# MAVCam.net
KiCad netlist of a schematic drawn in EAGLE
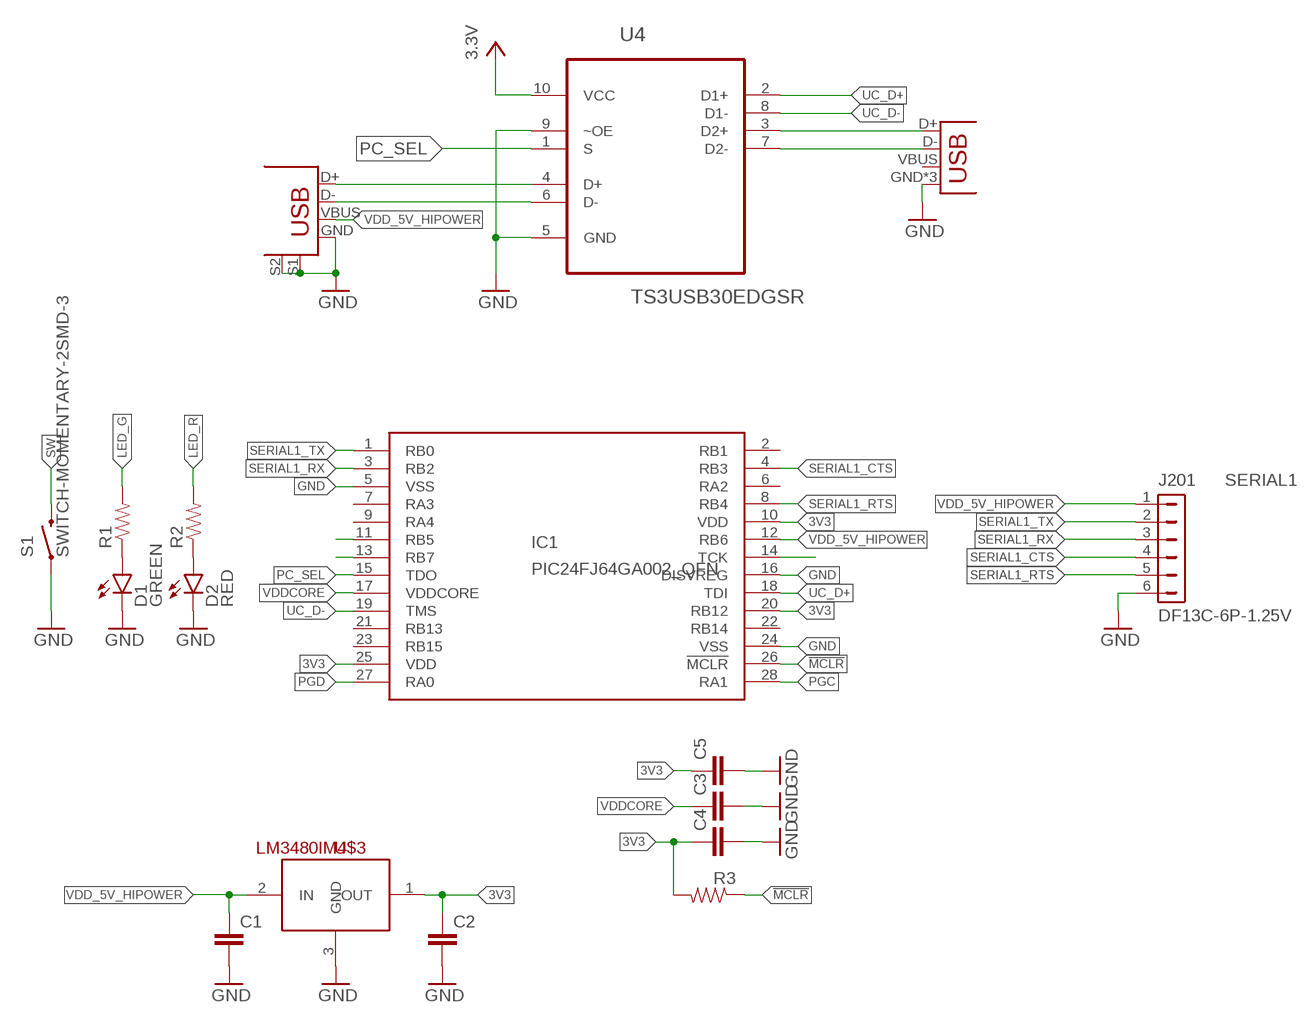
[diagram p0: schematic, sheet 1]

(export (version "E")
  (design (tool "Eeschema 10.0.6"))
  (components
    (comp (ref "C1")
      (value "CAP0603-CAP")
      (footprint "eagle-import:0603-CAP")
      (libsource (lib "eagle-import") (part "CAP0603-CAP"))
    )
    (comp (ref "C2")
      (value "CAP0603-CAP")
      (footprint "eagle-import:0603-CAP")
      (libsource (lib "eagle-import") (part "CAP0603-CAP"))
    )
    (comp (ref "C3")
      (value "CAP0603-CAP")
      (footprint "eagle-import:0603-CAP")
      (libsource (lib "eagle-import") (part "CAP0603-CAP"))
    )
    (comp (ref "C4")
      (value "CAP0603-CAP")
      (footprint "eagle-import:0603-CAP")
      (libsource (lib "eagle-import") (part "CAP0603-CAP"))
    )
    (comp (ref "C5")
      (value "CAP0603-CAP")
      (footprint "eagle-import:0603-CAP")
      (libsource (lib "eagle-import") (part "CAP0603-CAP"))
    )
    (comp (ref "D1")
      (value "GREEN")
      (footprint "eagle-import:LED-0603")
      (libsource (lib "eagle-import") (part "LED-GREEN0603"))
    )
    (comp (ref "D2")
      (value "RED")
      (footprint "eagle-import:LED-0603")
      (libsource (lib "eagle-import") (part "LED-RED0603"))
    )
    (comp (ref "IC1")
      (value "PIC24FJ64GA002_QFN")
      (footprint "eagle-import:QFN28-ML_6X6MM")
      (fields (field (name "MPN") "PIC24FJ64GA002-E/ML"))
      (libsource (lib "eagle-import") (part "PIC24FJ64GA002_QFN"))
    )
    (comp (ref "J201")
      (value "DF13C-6P-1.25V")
      (footprint "eagle-import:DF13C-6P-1.25V")
      (fields (field (name "PARTNO") "DF13C-6P-1.25V(20)"))
      (libsource (lib "eagle-import") (part "DF13-6P-1.25V"))
    )
    (comp (ref "JP1")
      (value "USB-MICROB")
      (footprint "eagle-import:USB-MICROB")
      (libsource (lib "eagle-import") (part "USB-MICROB"))
    )
    (comp (ref "R1")
      (value "RESISTOR0603-RES")
      (footprint "eagle-import:0603-RES")
      (libsource (lib "eagle-import") (part "RESISTOR0603-RES"))
    )
    (comp (ref "R2")
      (value "RESISTOR0603-RES")
      (footprint "eagle-import:0603-RES")
      (libsource (lib "eagle-import") (part "RESISTOR0603-RES"))
    )
    (comp (ref "R3")
      (value "RESISTOR0603-RES")
      (footprint "eagle-import:0603-RES")
      (libsource (lib "eagle-import") (part "RESISTOR0603-RES"))
    )
    (comp (ref "S1")
      (value "SWITCH-MOMENTARY-2SMD-3")
      (footprint "eagle-import:TACTILE_SWITCH_SMD-3")
      (libsource (lib "eagle-import") (part "SWITCH-MOMENTARY-2SMD-3"))
    )
    (comp (ref "U$1")
      (value "USB+SHIELDUSB-A-S-NOSILK-FEMALE")
      (footprint "eagle-import:USB-A-S-NOSILK-FEMALE")
      (libsource (lib "eagle-import") (part "USB+SHIELDUSB-A-S-NOSILK-FEMALE"))
    )
    (comp (ref "U$3")
      (value "LM3480IM4")
      (footprint "eagle-import:SOT23-3")
      (libsource (lib "eagle-import") (part "LM3480IM4"))
    )
    (comp (ref "U4")
      (value "TS3USB30EDGSR")
      (footprint "eagle-import:SOP50P490X110-10N")
      (libsource (lib "eagle-import") (part "TS3USB30EDGSR"))
    )
  )
  (nets
    (net (code "1") (name "/~{MCLR}") (class "Default")
      (node (ref "IC1") (pin "26") (pinfunction "~{MCLR}_26") (pintype "bidirectional"))
      (node (ref "R3") (pin "1") (pinfunction "1_1") (pintype "passive"))
    )
    (net (code "2") (name "3V3") (class "Default")
      (node (ref "C2") (pin "1") (pinfunction "1_1") (pintype "passive"))
      (node (ref "C4") (pin "1") (pinfunction "1_1") (pintype "passive"))
      (node (ref "C5") (pin "1") (pinfunction "1_1") (pintype "passive"))
      (node (ref "IC1") (pin "10") (pinfunction "VDD_10") (pintype "power_in"))
      (node (ref "IC1") (pin "20") (pinfunction "RB12_20") (pintype "bidirectional"))
      (node (ref "IC1") (pin "25") (pinfunction "VDD_25") (pintype "power_in"))
      (node (ref "R3") (pin "2") (pinfunction "2_2") (pintype "passive"))
      (node (ref "U$3") (pin "1") (pinfunction "OUT_1") (pintype "bidirectional"))
      (node (ref "U4") (pin "10") (pinfunction "VCC_10") (pintype "power_in"))
    )
    (net (code "3") (name "GND") (class "Default")
      (node (ref "C1") (pin "2") (pinfunction "2_2") (pintype "passive"))
      (node (ref "C2") (pin "2") (pinfunction "2_2") (pintype "passive"))
      (node (ref "C3") (pin "2") (pinfunction "2_2") (pintype "passive"))
      (node (ref "C4") (pin "2") (pinfunction "2_2") (pintype "passive"))
      (node (ref "C5") (pin "2") (pinfunction "2_2") (pintype "passive"))
      (node (ref "D1") (pin "C") (pinfunction "C_C") (pintype "passive"))
      (node (ref "D2") (pin "C") (pinfunction "C_C") (pintype "passive"))
      (node (ref "IC1") (pin "16") (pinfunction "DISVREG_16") (pintype "passive"))
      (node (ref "IC1") (pin "24") (pinfunction "VSS_24") (pintype "power_in"))
      (node (ref "IC1") (pin "5") (pinfunction "VSS_5") (pintype "power_in"))
      (node (ref "J201") (pin "6") (pinfunction "6_6") (pintype "passive"))
      (node (ref "JP1") (pin "GND") (pinfunction "GND_GND") (pintype "bidirectional"))
      (node (ref "JP1") (pin "MT1") (pinfunction "GND_MT1") (pintype "bidirectional"))
      (node (ref "JP1") (pin "MT2") (pinfunction "GND_MT2") (pintype "bidirectional"))
      (node (ref "S1") (pin "1") (pinfunction "1_1") (pintype "passive"))
      (node (ref "U$1") (pin "GND") (pinfunction "GND_GND") (pintype "bidirectional"))
      (node (ref "U$1") (pin "S1") (pinfunction "S1_S1") (pintype "bidirectional"))
      (node (ref "U$1") (pin "S2") (pinfunction "S2_S2") (pintype "bidirectional"))
      (node (ref "U$3") (pin "3") (pinfunction "GND_3") (pintype "bidirectional"))
      (node (ref "U4") (pin "5") (pinfunction "GND_5") (pintype "passive"))
      (node (ref "U4") (pin "9") (pinfunction "~{OE}_9") (pintype "input"))
    )
    (net (code "4") (name "LED_G") (class "Default")
      (node (ref "IC1") (pin "13") (pinfunction "RB7_13") (pintype "bidirectional"))
      (node (ref "R1") (pin "2") (pinfunction "2_2") (pintype "passive"))
    )
    (net (code "5") (name "LED_R") (class "Default")
      (node (ref "IC1") (pin "11") (pinfunction "RB5_11") (pintype "bidirectional"))
      (node (ref "R2") (pin "2") (pinfunction "2_2") (pintype "passive"))
    )
    (net (code "6") (name "Net-(D1-PadA)") (class "Default")
      (node (ref "D1") (pin "A") (pinfunction "A_A") (pintype "passive"))
      (node (ref "R1") (pin "1") (pinfunction "1_1") (pintype "passive"))
    )
    (net (code "7") (name "Net-(D2-PadA)") (class "Default")
      (node (ref "D2") (pin "A") (pinfunction "A_A") (pintype "passive"))
      (node (ref "R2") (pin "1") (pinfunction "1_1") (pintype "passive"))
    )
    (net (code "8") (name "Net-(U4-D+)") (class "Default")
      (node (ref "U$1") (pin "D+") (pinfunction "D+_D+") (pintype "bidirectional"))
      (node (ref "U4") (pin "4") (pinfunction "D+_4") (pintype "bidirectional"))
    )
    (net (code "9") (name "Net-(U4-D-)") (class "Default")
      (node (ref "U$1") (pin "D-") (pinfunction "D-_D-") (pintype "bidirectional"))
      (node (ref "U4") (pin "6") (pinfunction "D-_6") (pintype "bidirectional"))
    )
    (net (code "10") (name "Net-(U4-D2+)") (class "Default")
      (node (ref "JP1") (pin "D+") (pinfunction "D+_D+") (pintype "bidirectional"))
      (node (ref "U4") (pin "3") (pinfunction "D2+_3") (pintype "bidirectional"))
    )
    (net (code "11") (name "Net-(U4-D2-)") (class "Default")
      (node (ref "JP1") (pin "D-") (pinfunction "D-_D-") (pintype "bidirectional"))
      (node (ref "U4") (pin "7") (pinfunction "D2-_7") (pintype "bidirectional"))
    )
    (net (code "12") (name "PC_SEL") (class "Default")
      (node (ref "IC1") (pin "15") (pinfunction "TDO_15") (pintype "output"))
      (node (ref "U4") (pin "1") (pinfunction "S_1") (pintype "input"))
    )
    (net (code "13") (name "PGC") (class "Default")
      (node (ref "IC1") (pin "28") (pinfunction "RA1_28") (pintype "bidirectional"))
    )
    (net (code "14") (name "PGD") (class "Default")
      (node (ref "IC1") (pin "27") (pinfunction "RA0_27") (pintype "bidirectional"))
    )
    (net (code "15") (name "SERIAL1_CTS") (class "Default")
      (node (ref "IC1") (pin "4") (pinfunction "RB3_4") (pintype "bidirectional"))
      (node (ref "J201") (pin "4") (pinfunction "4_4") (pintype "passive"))
    )
    (net (code "16") (name "SERIAL1_RTS") (class "Default")
      (node (ref "IC1") (pin "8") (pinfunction "RB4_8") (pintype "bidirectional"))
      (node (ref "J201") (pin "5") (pinfunction "5_5") (pintype "passive"))
    )
    (net (code "17") (name "SERIAL1_RX") (class "Default")
      (node (ref "IC1") (pin "3") (pinfunction "RB2_3") (pintype "bidirectional"))
      (node (ref "J201") (pin "3") (pinfunction "3_3") (pintype "passive"))
    )
    (net (code "18") (name "SERIAL1_TX") (class "Default")
      (node (ref "IC1") (pin "1") (pinfunction "RB0_1") (pintype "bidirectional"))
      (node (ref "J201") (pin "2") (pinfunction "2_2") (pintype "passive"))
    )
    (net (code "19") (name "SW") (class "Default")
      (node (ref "IC1") (pin "14") (pinfunction "TCK_14") (pintype "input"))
      (node (ref "S1") (pin "4") (pinfunction "2_4") (pintype "passive"))
    )
    (net (code "20") (name "UC_D+") (class "Default")
      (node (ref "IC1") (pin "18") (pinfunction "TDI_18") (pintype "input"))
      (node (ref "U4") (pin "2") (pinfunction "D1+_2") (pintype "bidirectional"))
    )
    (net (code "21") (name "UC_D-") (class "Default")
      (node (ref "IC1") (pin "19") (pinfunction "TMS_19") (pintype "input"))
      (node (ref "U4") (pin "8") (pinfunction "D1-_8") (pintype "bidirectional"))
    )
    (net (code "22") (name "VDDCORE") (class "Default")
      (node (ref "C3") (pin "1") (pinfunction "1_1") (pintype "passive"))
      (node (ref "IC1") (pin "17") (pinfunction "VDDCORE_17") (pintype "power_in"))
    )
    (net (code "23") (name "VDD_5V_HIPOWER") (class "Default")
      (node (ref "C1") (pin "1") (pinfunction "1_1") (pintype "passive"))
      (node (ref "IC1") (pin "12") (pinfunction "RB6_12") (pintype "bidirectional"))
      (node (ref "J201") (pin "1") (pinfunction "1_1") (pintype "passive"))
      (node (ref "U$1") (pin "VBUS") (pinfunction "VBUS_VBUS") (pintype "bidirectional"))
      (node (ref "U$3") (pin "2") (pinfunction "IN_2") (pintype "bidirectional"))
    )
    (net (code "24") (name "unconnected-(IC1-RA2-Pad6)") (class "Default")
      (node (ref "IC1") (pin "6") (pinfunction "RA2_6") (pintype "bidirectional"))
    )
    (net (code "25") (name "unconnected-(IC1-RA3-Pad7)") (class "Default")
      (node (ref "IC1") (pin "7") (pinfunction "RA3_7") (pintype "bidirectional"))
    )
    (net (code "26") (name "unconnected-(IC1-RA4-Pad9)") (class "Default")
      (node (ref "IC1") (pin "9") (pinfunction "RA4_9") (pintype "bidirectional"))
    )
    (net (code "27") (name "unconnected-(IC1-RB1-Pad2)") (class "Default")
      (node (ref "IC1") (pin "2") (pinfunction "RB1_2") (pintype "bidirectional"))
    )
    (net (code "28") (name "unconnected-(IC1-RB13-Pad21)") (class "Default")
      (node (ref "IC1") (pin "21") (pinfunction "RB13_21") (pintype "bidirectional"))
    )
    (net (code "29") (name "unconnected-(IC1-RB14-Pad22)") (class "Default")
      (node (ref "IC1") (pin "22") (pinfunction "RB14_22") (pintype "bidirectional"))
    )
    (net (code "30") (name "unconnected-(IC1-RB15-Pad23)") (class "Default")
      (node (ref "IC1") (pin "23") (pinfunction "RB15_23") (pintype "bidirectional"))
    )
    (net (code "31") (name "unconnected-(JP1-PadVBUS)") (class "Default")
      (node (ref "JP1") (pin "VBUS") (pinfunction "VBUS_VBUS") (pintype "bidirectional"))
    )
  )
)
